# mega.net
KiCad netlist of a schematic drawn in EAGLE
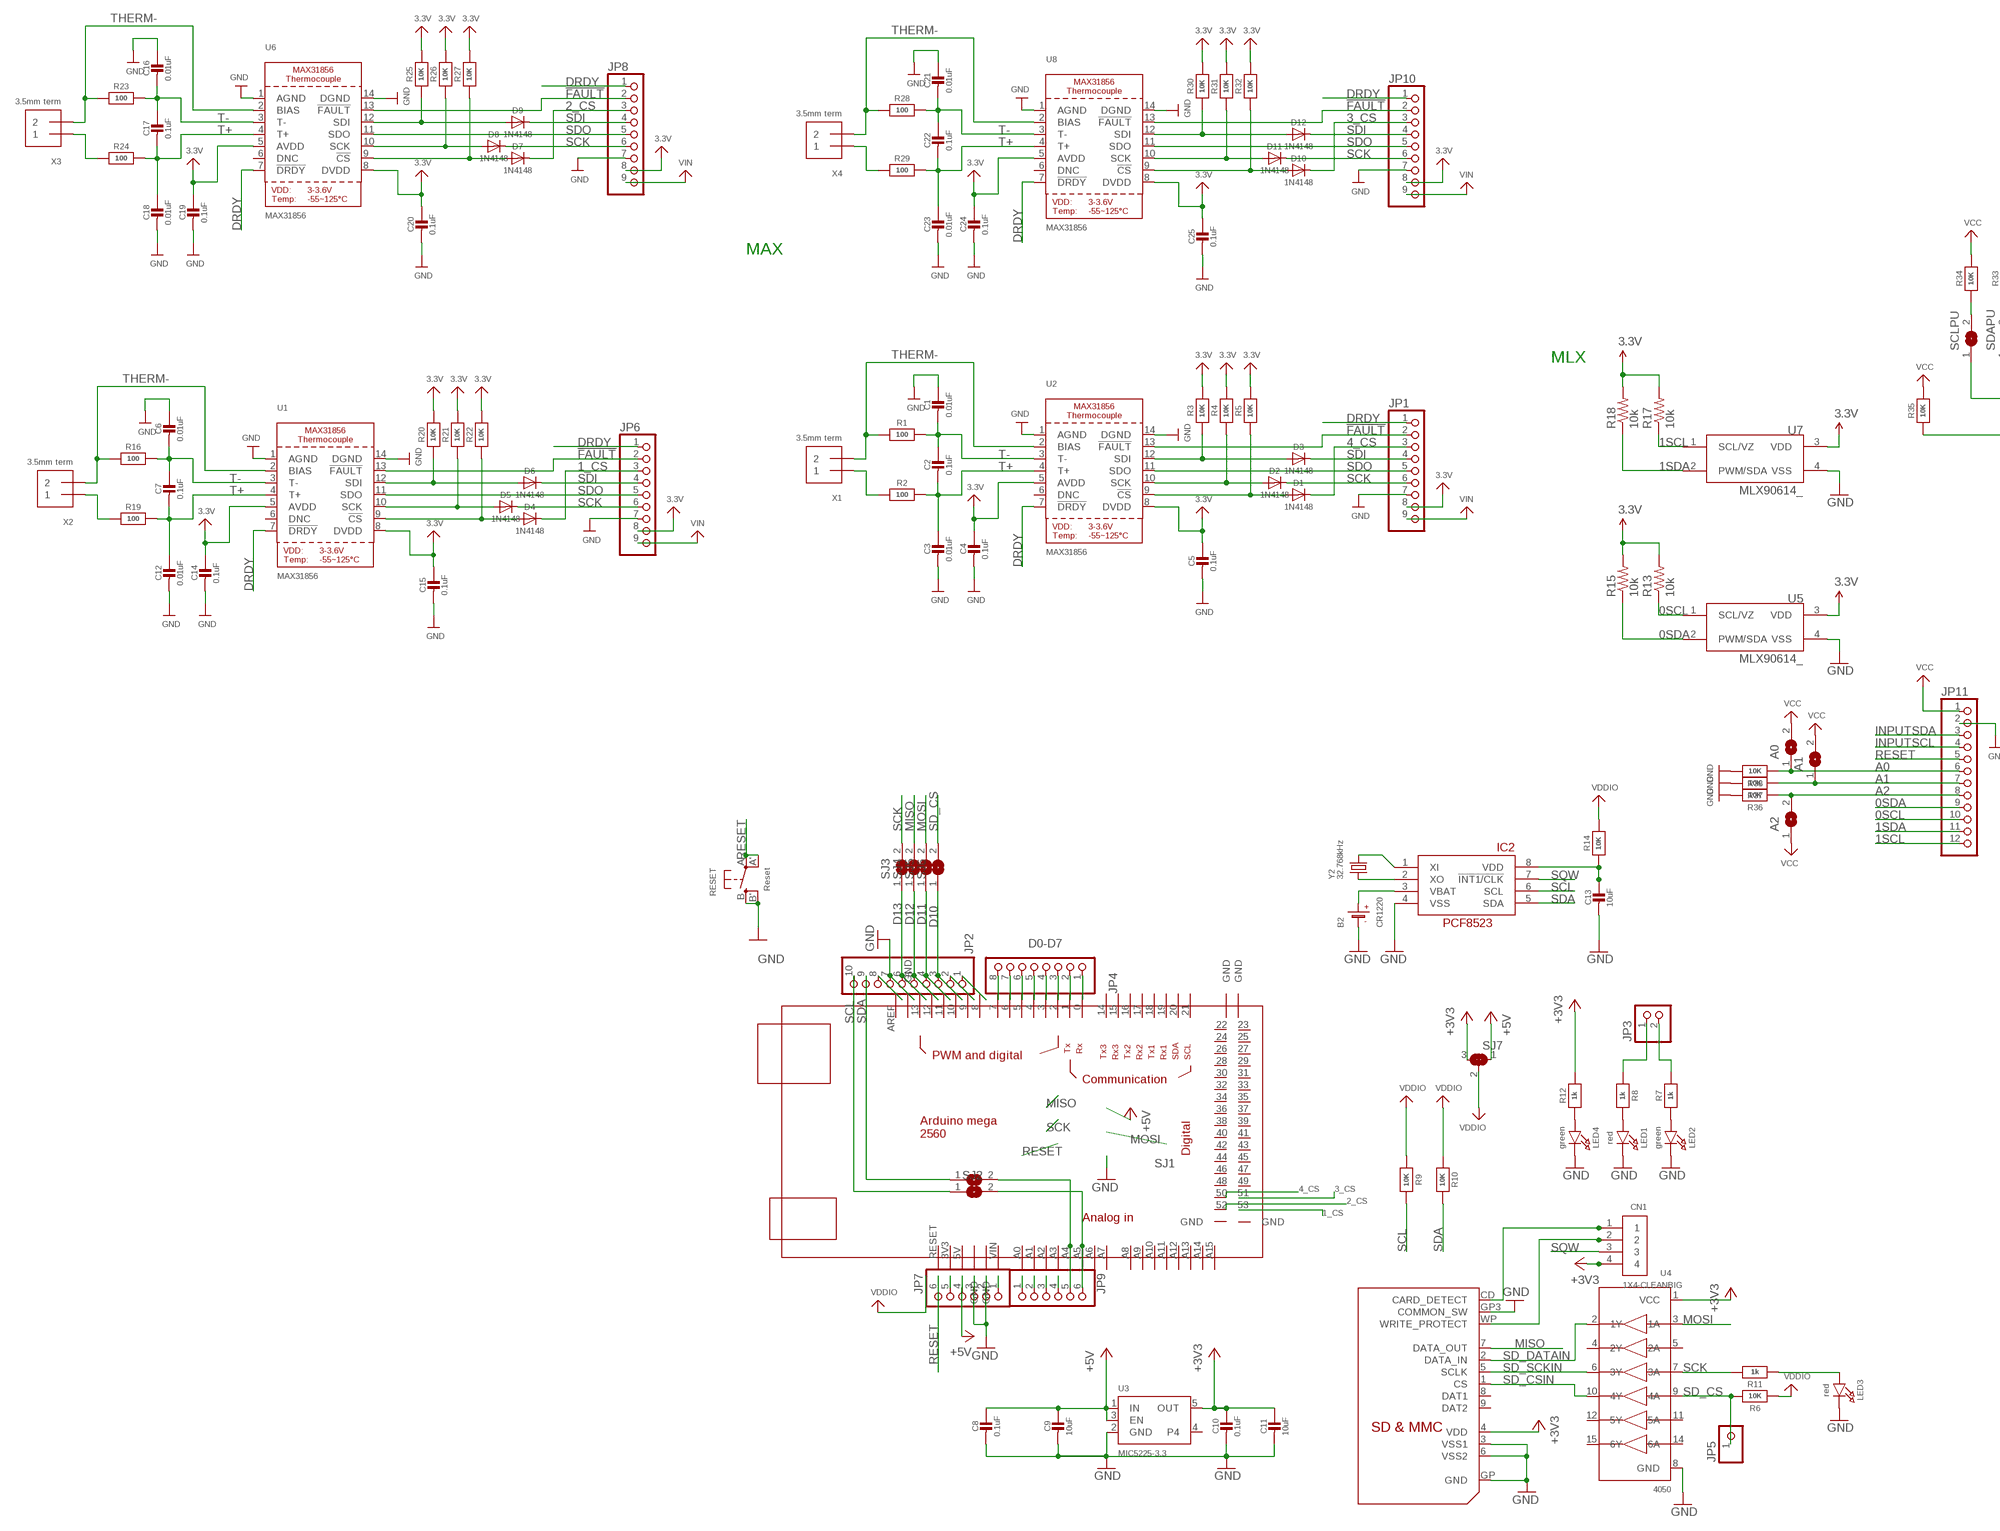
[diagram p0: schematic, sheet 1, part 1 of 2]
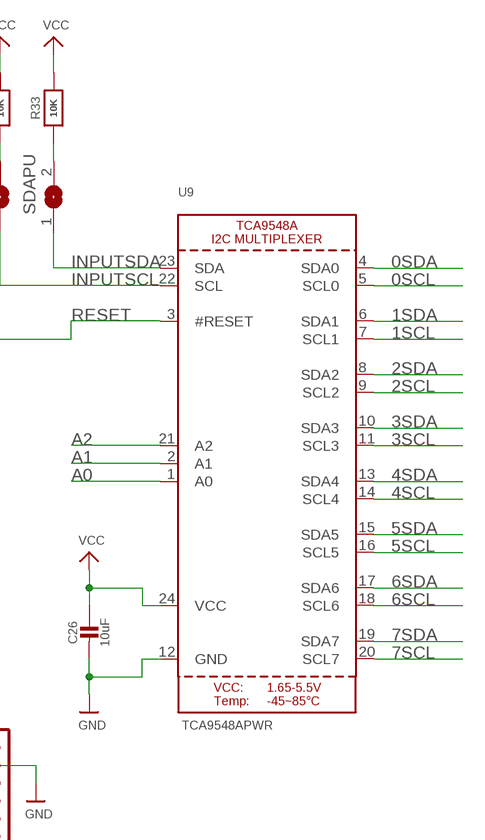
[diagram p1: schematic, sheet 1, part 2 of 2]

(export (version "E")
  (design (tool "Eeschema 10.0.6"))
  (components
    (comp (ref "A0")
      (value "SOLDERJUMPER")
      (footprint "eagle-import:SOLDERJUMPER_ARROW_NOPASTE")
      (libsource (lib "eagle-import") (part "SOLDERJUMPER"))
    )
    (comp (ref "A1")
      (value "SOLDERJUMPER")
      (footprint "eagle-import:SOLDERJUMPER_ARROW_NOPASTE")
      (libsource (lib "eagle-import") (part "SOLDERJUMPER"))
    )
    (comp (ref "A2")
      (value "SOLDERJUMPER")
      (footprint "eagle-import:SOLDERJUMPER_ARROW_NOPASTE")
      (libsource (lib "eagle-import") (part "SOLDERJUMPER"))
    )
    (comp (ref "B2")
      (value "CR1220")
      (footprint "eagle-import:CR1220")
      (libsource (lib "eagle-import") (part "BATTERYCR1220_SMT"))
    )
    (comp (ref "C1")
      (value "0.01uF")
      (footprint "eagle-import:0805_10MGAP")
      (libsource (lib "eagle-import") (part "CAP_CERAMIC0805_10MGAP"))
    )
    (comp (ref "C2")
      (value "0.1uF")
      (footprint "eagle-import:0805-NO")
      (libsource (lib "eagle-import") (part "CAP_CERAMIC0805-NOOUTLINE"))
    )
    (comp (ref "C3")
      (value "0.01uF")
      (footprint "eagle-import:0805-NO")
      (libsource (lib "eagle-import") (part "CAP_CERAMIC0805-NOOUTLINE"))
    )
    (comp (ref "C4")
      (value "0.1uF")
      (footprint "eagle-import:0805-NO")
      (libsource (lib "eagle-import") (part "CAP_CERAMIC0805-NOOUTLINE"))
    )
    (comp (ref "C5")
      (value "0.1uF")
      (footprint "eagle-import:0805-NO")
      (libsource (lib "eagle-import") (part "CAP_CERAMIC0805-NOOUTLINE"))
    )
    (comp (ref "C6")
      (value "0.01uF")
      (footprint "eagle-import:0805_10MGAP")
      (libsource (lib "eagle-import") (part "CAP_CERAMIC0805_10MGAP"))
    )
    (comp (ref "C7")
      (value "0.1uF")
      (footprint "eagle-import:0805-NO")
      (libsource (lib "eagle-import") (part "CAP_CERAMIC0805-NOOUTLINE"))
    )
    (comp (ref "C8")
      (value "0.1uF")
      (footprint "eagle-import:0805-NO")
      (libsource (lib "eagle-import") (part "CAP_CERAMIC0805-NOOUTLINE"))
    )
    (comp (ref "C9")
      (value "10uF")
      (footprint "eagle-import:0805-NO")
      (libsource (lib "eagle-import") (part "CAP_CERAMIC0805-NOOUTLINE"))
    )
    (comp (ref "C10")
      (value "0.1uF")
      (footprint "eagle-import:0805-NO")
      (libsource (lib "eagle-import") (part "CAP_CERAMIC0805-NOOUTLINE"))
    )
    (comp (ref "C11")
      (value "10uF")
      (footprint "eagle-import:0805-NO")
      (libsource (lib "eagle-import") (part "CAP_CERAMIC0805-NOOUTLINE"))
    )
    (comp (ref "C12")
      (value "0.01uF")
      (footprint "eagle-import:0805-NO")
      (libsource (lib "eagle-import") (part "CAP_CERAMIC0805-NOOUTLINE"))
    )
    (comp (ref "C13")
      (value "10uF")
      (footprint "eagle-import:0805-NO")
      (libsource (lib "eagle-import") (part "CAP_CERAMIC0805-NOOUTLINE"))
    )
    (comp (ref "C14")
      (value "0.1uF")
      (footprint "eagle-import:0805-NO")
      (libsource (lib "eagle-import") (part "CAP_CERAMIC0805-NOOUTLINE"))
    )
    (comp (ref "C15")
      (value "0.1uF")
      (footprint "eagle-import:0805-NO")
      (libsource (lib "eagle-import") (part "CAP_CERAMIC0805-NOOUTLINE"))
    )
    (comp (ref "C16")
      (value "0.01uF")
      (footprint "eagle-import:0805_10MGAP")
      (libsource (lib "eagle-import") (part "CAP_CERAMIC0805_10MGAP"))
    )
    (comp (ref "C17")
      (value "0.1uF")
      (footprint "eagle-import:0805-NO")
      (libsource (lib "eagle-import") (part "CAP_CERAMIC0805-NOOUTLINE"))
    )
    (comp (ref "C18")
      (value "0.01uF")
      (footprint "eagle-import:0805-NO")
      (libsource (lib "eagle-import") (part "CAP_CERAMIC0805-NOOUTLINE"))
    )
    (comp (ref "C19")
      (value "0.1uF")
      (footprint "eagle-import:0805-NO")
      (libsource (lib "eagle-import") (part "CAP_CERAMIC0805-NOOUTLINE"))
    )
    (comp (ref "C20")
      (value "0.1uF")
      (footprint "eagle-import:0805-NO")
      (libsource (lib "eagle-import") (part "CAP_CERAMIC0805-NOOUTLINE"))
    )
    (comp (ref "C21")
      (value "0.01uF")
      (footprint "eagle-import:0805_10MGAP")
      (libsource (lib "eagle-import") (part "CAP_CERAMIC0805_10MGAP"))
    )
    (comp (ref "C22")
      (value "0.1uF")
      (footprint "eagle-import:0805-NO")
      (libsource (lib "eagle-import") (part "CAP_CERAMIC0805-NOOUTLINE"))
    )
    (comp (ref "C23")
      (value "0.01uF")
      (footprint "eagle-import:0805-NO")
      (libsource (lib "eagle-import") (part "CAP_CERAMIC0805-NOOUTLINE"))
    )
    (comp (ref "C24")
      (value "0.1uF")
      (footprint "eagle-import:0805-NO")
      (libsource (lib "eagle-import") (part "CAP_CERAMIC0805-NOOUTLINE"))
    )
    (comp (ref "C25")
      (value "0.1uF")
      (footprint "eagle-import:0805-NO")
      (libsource (lib "eagle-import") (part "CAP_CERAMIC0805-NOOUTLINE"))
    )
    (comp (ref "C26")
      (value "10uF")
      (footprint "eagle-import:0805-NO")
      (libsource (lib "eagle-import") (part "CAP_CERAMIC0805-NOOUTLINE"))
    )
    (comp (ref "CN1")
      (value "1X4-CLEANBIG")
      (footprint "eagle-import:1X04-CLEANBIG")
      (libsource (lib "eagle-import") (part "1X4-CLEANBIG"))
    )
    (comp (ref "D1")
      (value "1N4148")
      (footprint "eagle-import:SOD-323")
      (libsource (lib "eagle-import") (part "DIODESOD-323"))
    )
    (comp (ref "D2")
      (value "1N4148")
      (footprint "eagle-import:SOD-323")
      (libsource (lib "eagle-import") (part "DIODESOD-323"))
    )
    (comp (ref "D3")
      (value "1N4148")
      (footprint "eagle-import:SOD-323")
      (libsource (lib "eagle-import") (part "DIODESOD-323"))
    )
    (comp (ref "D4")
      (value "1N4148")
      (footprint "eagle-import:SOD-323")
      (libsource (lib "eagle-import") (part "DIODESOD-323"))
    )
    (comp (ref "D5")
      (value "1N4148")
      (footprint "eagle-import:SOD-323")
      (libsource (lib "eagle-import") (part "DIODESOD-323"))
    )
    (comp (ref "D6")
      (value "1N4148")
      (footprint "eagle-import:SOD-323")
      (libsource (lib "eagle-import") (part "DIODESOD-323"))
    )
    (comp (ref "D7")
      (value "1N4148")
      (footprint "eagle-import:SOD-323")
      (libsource (lib "eagle-import") (part "DIODESOD-323"))
    )
    (comp (ref "D8")
      (value "1N4148")
      (footprint "eagle-import:SOD-323")
      (libsource (lib "eagle-import") (part "DIODESOD-323"))
    )
    (comp (ref "D9")
      (value "1N4148")
      (footprint "eagle-import:SOD-323")
      (libsource (lib "eagle-import") (part "DIODESOD-323"))
    )
    (comp (ref "D10")
      (value "1N4148")
      (footprint "eagle-import:SOD-323")
      (libsource (lib "eagle-import") (part "DIODESOD-323"))
    )
    (comp (ref "D11")
      (value "1N4148")
      (footprint "eagle-import:SOD-323")
      (libsource (lib "eagle-import") (part "DIODESOD-323"))
    )
    (comp (ref "D12")
      (value "1N4148")
      (footprint "eagle-import:SOD-323")
      (libsource (lib "eagle-import") (part "DIODESOD-323"))
    )
    (comp (ref "IC2")
      (value "PCF8523T")
      (footprint "eagle-import:SOIC8_150MIL")
      (libsource (lib "eagle-import") (part "RTC_PCF8523T"))
    )
    (comp (ref "JP1")
      (value "HEADER-1X970MIL")
      (footprint "eagle-import:1X09_ROUND_70")
      (libsource (lib "eagle-import") (part "HEADER-1X970MIL"))
    )
    (comp (ref "JP2")
      (value "HEADER-1X1070MIL")
      (footprint "eagle-import:1X10_ROUND70")
      (libsource (lib "eagle-import") (part "HEADER-1X1070MIL"))
    )
    (comp (ref "JP3")
      (value "HEADER-1X2ROUND")
      (footprint "eagle-import:1X02_ROUND")
      (libsource (lib "eagle-import") (part "HEADER-1X2ROUND"))
    )
    (comp (ref "JP4")
      (value "D0-D7")
      (footprint "eagle-import:1X08-BIG")
      (libsource (lib "eagle-import") (part "PINHD-1X8BIG"))
    )
    (comp (ref "JP5")
      (value "HEADER-1X1ROUND")
      (footprint "eagle-import:1X01_ROUND")
      (libsource (lib "eagle-import") (part "HEADER-1X1ROUND"))
    )
    (comp (ref "JP6")
      (value "HEADER-1X970MIL")
      (footprint "eagle-import:1X09_ROUND_70")
      (libsource (lib "eagle-import") (part "HEADER-1X970MIL"))
    )
    (comp (ref "JP7")
      (value "PINHD-1X6B")
      (footprint "eagle-import:1X06-BIG")
      (libsource (lib "eagle-import") (part "PINHD-1X6B"))
    )
    (comp (ref "JP8")
      (value "HEADER-1X970MIL")
      (footprint "eagle-import:1X09_ROUND_70")
      (libsource (lib "eagle-import") (part "HEADER-1X970MIL"))
    )
    (comp (ref "JP9")
      (value "PINHD-1X6B")
      (footprint "eagle-import:1X06-BIG")
      (libsource (lib "eagle-import") (part "PINHD-1X6B"))
    )
    (comp (ref "JP10")
      (value "HEADER-1X970MIL")
      (footprint "eagle-import:1X09_ROUND_70")
      (libsource (lib "eagle-import") (part "HEADER-1X970MIL"))
    )
    (comp (ref "JP11")
      (value "HEADER-1X12")
      (footprint "eagle-import:1X12_ROUND")
      (libsource (lib "eagle-import") (part "HEADER-1X12"))
    )
    (comp (ref "LED1")
      (value "red")
      (footprint "eagle-import:CHIPLED_0805_NOOUTLINE")
      (libsource (lib "eagle-import") (part "LED0805_NOOUTLINE"))
    )
    (comp (ref "LED2")
      (value "green")
      (footprint "eagle-import:CHIPLED_0805_NOOUTLINE")
      (libsource (lib "eagle-import") (part "LED0805_NOOUTLINE"))
    )
    (comp (ref "LED3")
      (value "red")
      (footprint "eagle-import:CHIPLED_0805_NOOUTLINE")
      (libsource (lib "eagle-import") (part "LED0805_NOOUTLINE"))
    )
    (comp (ref "LED4")
      (value "green")
      (footprint "eagle-import:CHIPLED_0805_NOOUTLINE")
      (libsource (lib "eagle-import") (part "LED0805_NOOUTLINE"))
    )
    (comp (ref "R1")
      (value "100")
      (footprint "eagle-import:0805-NO")
      (libsource (lib "eagle-import") (part "RESISTOR0805_NOOUTLINE"))
    )
    (comp (ref "R2")
      (value "100")
      (footprint "eagle-import:0805-NO")
      (libsource (lib "eagle-import") (part "RESISTOR0805_NOOUTLINE"))
    )
    (comp (ref "R3")
      (value "10K")
      (footprint "eagle-import:0805-NO")
      (libsource (lib "eagle-import") (part "RESISTOR0805_NOOUTLINE"))
    )
    (comp (ref "R4")
      (value "10K")
      (footprint "eagle-import:0805-NO")
      (libsource (lib "eagle-import") (part "RESISTOR0805_NOOUTLINE"))
    )
    (comp (ref "R5")
      (value "10K")
      (footprint "eagle-import:0805-NO")
      (libsource (lib "eagle-import") (part "RESISTOR0805_NOOUTLINE"))
    )
    (comp (ref "R6")
      (value "10K")
      (footprint "eagle-import:0805-NO")
      (libsource (lib "eagle-import") (part "RESISTOR0805_NOOUTLINE"))
    )
    (comp (ref "R7")
      (value "1k")
      (footprint "eagle-import:0805-NO")
      (libsource (lib "eagle-import") (part "RESISTOR0805_NOOUTLINE"))
    )
    (comp (ref "R8")
      (value "1k")
      (footprint "eagle-import:0805-NO")
      (libsource (lib "eagle-import") (part "RESISTOR0805_NOOUTLINE"))
    )
    (comp (ref "R9")
      (value "10K")
      (footprint "eagle-import:0805-NO")
      (libsource (lib "eagle-import") (part "RESISTOR0805_NOOUTLINE"))
    )
    (comp (ref "R10")
      (value "10K")
      (footprint "eagle-import:0805-NO")
      (libsource (lib "eagle-import") (part "RESISTOR0805_NOOUTLINE"))
    )
    (comp (ref "R11")
      (value "1k")
      (footprint "eagle-import:0805-NO")
      (libsource (lib "eagle-import") (part "RESISTOR0805_NOOUTLINE"))
    )
    (comp (ref "R12")
      (value "1k")
      (footprint "eagle-import:0805-NO")
      (libsource (lib "eagle-import") (part "RESISTOR0805_NOOUTLINE"))
    )
    (comp (ref "R13")
      (value "10k")
      (footprint "eagle-import:0402-RES")
      (libsource (lib "eagle-import") (part "RESISTOR0402-RES"))
    )
    (comp (ref "R14")
      (value "10K")
      (footprint "eagle-import:0805-NO")
      (libsource (lib "eagle-import") (part "RESISTOR0805_NOOUTLINE"))
    )
    (comp (ref "R15")
      (value "10k")
      (footprint "eagle-import:0402-RES")
      (libsource (lib "eagle-import") (part "RESISTOR0402-RES"))
    )
    (comp (ref "R16")
      (value "100")
      (footprint "eagle-import:0805-NO")
      (libsource (lib "eagle-import") (part "RESISTOR0805_NOOUTLINE"))
    )
    (comp (ref "R17")
      (value "10k")
      (footprint "eagle-import:0402-RES")
      (libsource (lib "eagle-import") (part "RESISTOR0402-RES"))
    )
    (comp (ref "R18")
      (value "10k")
      (footprint "eagle-import:0402-RES")
      (libsource (lib "eagle-import") (part "RESISTOR0402-RES"))
    )
    (comp (ref "R19")
      (value "100")
      (footprint "eagle-import:0805-NO")
      (libsource (lib "eagle-import") (part "RESISTOR0805_NOOUTLINE"))
    )
    (comp (ref "R20")
      (value "10K")
      (footprint "eagle-import:0805-NO")
      (libsource (lib "eagle-import") (part "RESISTOR0805_NOOUTLINE"))
    )
    (comp (ref "R21")
      (value "10K")
      (footprint "eagle-import:0805-NO")
      (libsource (lib "eagle-import") (part "RESISTOR0805_NOOUTLINE"))
    )
    (comp (ref "R22")
      (value "10K")
      (footprint "eagle-import:0805-NO")
      (libsource (lib "eagle-import") (part "RESISTOR0805_NOOUTLINE"))
    )
    (comp (ref "R23")
      (value "100")
      (footprint "eagle-import:0805-NO")
      (libsource (lib "eagle-import") (part "RESISTOR0805_NOOUTLINE"))
    )
    (comp (ref "R24")
      (value "100")
      (footprint "eagle-import:0805-NO")
      (libsource (lib "eagle-import") (part "RESISTOR0805_NOOUTLINE"))
    )
    (comp (ref "R25")
      (value "10K")
      (footprint "eagle-import:0805-NO")
      (libsource (lib "eagle-import") (part "RESISTOR0805_NOOUTLINE"))
    )
    (comp (ref "R26")
      (value "10K")
      (footprint "eagle-import:0805-NO")
      (libsource (lib "eagle-import") (part "RESISTOR0805_NOOUTLINE"))
    )
    (comp (ref "R27")
      (value "10K")
      (footprint "eagle-import:0805-NO")
      (libsource (lib "eagle-import") (part "RESISTOR0805_NOOUTLINE"))
    )
    (comp (ref "R28")
      (value "100")
      (footprint "eagle-import:0805-NO")
      (libsource (lib "eagle-import") (part "RESISTOR0805_NOOUTLINE"))
    )
    (comp (ref "R29")
      (value "100")
      (footprint "eagle-import:0805-NO")
      (libsource (lib "eagle-import") (part "RESISTOR0805_NOOUTLINE"))
    )
    (comp (ref "R30")
      (value "10K")
      (footprint "eagle-import:0805-NO")
      (libsource (lib "eagle-import") (part "RESISTOR0805_NOOUTLINE"))
    )
    (comp (ref "R31")
      (value "10K")
      (footprint "eagle-import:0805-NO")
      (libsource (lib "eagle-import") (part "RESISTOR0805_NOOUTLINE"))
    )
    (comp (ref "R32")
      (value "10K")
      (footprint "eagle-import:0805-NO")
      (libsource (lib "eagle-import") (part "RESISTOR0805_NOOUTLINE"))
    )
    (comp (ref "R33")
      (value "10K")
      (footprint "eagle-import:0805-NO")
      (libsource (lib "eagle-import") (part "RESISTOR0805_NOOUTLINE"))
    )
    (comp (ref "R34")
      (value "10K")
      (footprint "eagle-import:0805-NO")
      (libsource (lib "eagle-import") (part "RESISTOR0805_NOOUTLINE"))
    )
    (comp (ref "R35")
      (value "10K")
      (footprint "eagle-import:_0805MP")
      (libsource (lib "eagle-import") (part "RESISTOR_0805MP"))
    )
    (comp (ref "R36")
      (value "10K")
      (footprint "eagle-import:0805-NO")
      (libsource (lib "eagle-import") (part "RESISTOR0805_NOOUTLINE"))
    )
    (comp (ref "R37")
      (value "10K")
      (footprint "eagle-import:0805-NO")
      (libsource (lib "eagle-import") (part "RESISTOR0805_NOOUTLINE"))
    )
    (comp (ref "R38")
      (value "10K")
      (footprint "eagle-import:0805-NO")
      (libsource (lib "eagle-import") (part "RESISTOR0805_NOOUTLINE"))
    )
    (comp (ref "RESET")
      (value "Reset")
      (footprint "eagle-import:EVQ-Q2_SMALLER")
      (libsource (lib "eagle-import") (part "SWITCH_TACT_SMT_EVQQ2_SMALL"))
    )
    (comp (ref "SCLPU")
      (value "SOLDERJUMPERCLOSED")
      (footprint "eagle-import:SOLDERJUMPER_CLOSEDWIRE")
      (libsource (lib "eagle-import") (part "SOLDERJUMPERCLOSED"))
    )
    (comp (ref "SDAPU")
      (value "SOLDERJUMPERCLOSED")
      (footprint "eagle-import:SOLDERJUMPER_CLOSEDWIRE")
      (libsource (lib "eagle-import") (part "SOLDERJUMPERCLOSED"))
    )
    (comp (ref "SJ1")
      (value "SOLDERJUMPER")
      (footprint "eagle-import:SOLDERJUMPER_ARROW_NOPASTE")
      (libsource (lib "eagle-import") (part "SOLDERJUMPER"))
    )
    (comp (ref "SJ2")
      (value "SOLDERJUMPER")
      (footprint "eagle-import:SOLDERJUMPER_ARROW_NOPASTE")
      (libsource (lib "eagle-import") (part "SOLDERJUMPER"))
    )
    (comp (ref "SJ3")
      (value "SOLDERJUMPER")
      (footprint "eagle-import:SOLDERJUMPER_ARROW_NOPASTE")
      (libsource (lib "eagle-import") (part "SOLDERJUMPER"))
    )
    (comp (ref "SJ4")
      (value "SOLDERJUMPER")
      (footprint "eagle-import:SOLDERJUMPER_ARROW_NOPASTE")
      (libsource (lib "eagle-import") (part "SOLDERJUMPER"))
    )
    (comp (ref "SJ5")
      (value "SOLDERJUMPER")
      (footprint "eagle-import:SOLDERJUMPER_ARROW_NOPASTE")
      (libsource (lib "eagle-import") (part "SOLDERJUMPER"))
    )
    (comp (ref "SJ6")
      (value "SOLDERJUMPERCLOSED")
      (footprint "eagle-import:SOLDERJUMPER_CLOSEDWIRE")
      (libsource (lib "eagle-import") (part "SOLDERJUMPERCLOSED"))
    )
    (comp (ref "SJ7")
      (value "SOLDERJUMPER_2WAY")
      (footprint "eagle-import:SOLDERJUMPER_2WAY_OPEN_NOPASTE")
      (libsource (lib "eagle-import") (part "SOLDERJUMPER_2WAY"))
    )
    (comp (ref "U$1")
      (value "MEGA_DEVICE")
      (footprint "eagle-import:MEGAOUTLINE")
      (libsource (lib "eagle-import") (part "MEGA_DEVICE"))
    )
    (comp (ref "U$14")
      (value "SDMMC06132")
      (footprint "eagle-import:06132")
      (libsource (lib "eagle-import") (part "SDMMC06132"))
    )
    (comp (ref "U1")
      (value "MAX31856")
      (footprint "eagle-import:TSSOP14")
      (libsource (lib "eagle-import") (part "MAX31856"))
    )
    (comp (ref "U2")
      (value "MAX31856")
      (footprint "eagle-import:TSSOP14")
      (libsource (lib "eagle-import") (part "MAX31856"))
    )
    (comp (ref "U3")
      (value "MIC5225-3.3")
      (footprint "eagle-import:SOT23-5")
      (libsource (lib "eagle-import") (part "VREG_SOT23-5"))
    )
    (comp (ref "U4")
      (value "4050")
      (footprint "eagle-import:SOIC16")
      (libsource (lib "eagle-import") (part "74HC4050D"))
    )
    (comp (ref "U5")
      (value "MLX90614_")
      (footprint "eagle-import:TO-39")
      (libsource (lib "eagle-import") (part "MLX90614_"))
    )
    (comp (ref "U6")
      (value "MAX31856")
      (footprint "eagle-import:TSSOP14")
      (libsource (lib "eagle-import") (part "MAX31856"))
    )
    (comp (ref "U7")
      (value "MLX90614_")
      (footprint "eagle-import:TO-39")
      (libsource (lib "eagle-import") (part "MLX90614_"))
    )
    (comp (ref "U8")
      (value "MAX31856")
      (footprint "eagle-import:TSSOP14")
      (libsource (lib "eagle-import") (part "MAX31856"))
    )
    (comp (ref "U9")
      (value "TCA9548APWR")
      (footprint "eagle-import:TSSOP24")
      (libsource (lib "eagle-import") (part "TCA9548A"))
    )
    (comp (ref "X1")
      (value "3.5mm term")
      (footprint "eagle-import:TERMBLOCK_1X2-3.5MM")
      (libsource (lib "eagle-import") (part "TERMBLOCK_1X2"))
    )
    (comp (ref "X2")
      (value "3.5mm term")
      (footprint "eagle-import:TERMBLOCK_1X2-3.5MM")
      (libsource (lib "eagle-import") (part "TERMBLOCK_1X2"))
    )
    (comp (ref "X3")
      (value "3.5mm term")
      (footprint "eagle-import:TERMBLOCK_1X2-3.5MM")
      (libsource (lib "eagle-import") (part "TERMBLOCK_1X2"))
    )
    (comp (ref "X4")
      (value "3.5mm term")
      (footprint "eagle-import:TERMBLOCK_1X2-3.5MM")
      (libsource (lib "eagle-import") (part "TERMBLOCK_1X2"))
    )
    (comp (ref "Y2")
      (value "32.768kHz")
      (footprint "eagle-import:CRYSTAL_8X3.8")
      (libsource (lib "eagle-import") (part "CRYSTAL8.0X3.8"))
    )
  )
  (nets
    (net (code "1") (name "+3V3") (class "Default")
      (node (ref "C10") (pin "1") (pinfunction "1_1") (pintype "passive"))
      (node (ref "C11") (pin "1") (pinfunction "1_1") (pintype "passive"))
      (node (ref "CN1") (pin "4") (pinfunction "4_4") (pintype "bidirectional"))
      (node (ref "R12") (pin "2") (pinfunction "2_2") (pintype "passive"))
      (node (ref "SJ7") (pin "3") (pinfunction "3_3") (pintype "passive"))
      (node (ref "U$14") (pin "4") (pinfunction "VDD_4") (pintype "power_in"))
      (node (ref "U3") (pin "5") (pinfunction "OUT_5") (pintype "power_in"))
      (node (ref "U4") (pin "1") (pinfunction "VCC_1") (pintype "bidirectional"))
    )
    (net (code "2") (name "+5V") (class "Default")
      (node (ref "C8") (pin "1") (pinfunction "1_1") (pintype "passive"))
      (node (ref "C9") (pin "1") (pinfunction "1_1") (pintype "passive"))
      (node (ref "JP7") (pin "4") (pinfunction "4_4") (pintype "passive"))
      (node (ref "SJ7") (pin "1") (pinfunction "1_1") (pintype "passive"))
      (node (ref "U3") (pin "1") (pinfunction "IN_1") (pintype "power_in"))
      (node (ref "U3") (pin "3") (pinfunction "EN_3") (pintype "input"))
    )
    (net (code "3") (name "/0SCL") (class "Default")
      (node (ref "JP11") (pin "10") (pinfunction "10_10") (pintype "passive"))
      (node (ref "R13") (pin "1") (pinfunction "1_1") (pintype "passive"))
      (node (ref "U5") (pin "1") (pinfunction "SCL/VZ_1") (pintype "bidirectional"))
      (node (ref "U9") (pin "5") (pinfunction "SCL0_5") (pintype "bidirectional"))
    )
    (net (code "4") (name "/0SDA") (class "Default")
      (node (ref "JP11") (pin "9") (pinfunction "9_9") (pintype "passive"))
      (node (ref "R15") (pin "1") (pinfunction "1_1") (pintype "passive"))
      (node (ref "U5") (pin "2") (pinfunction "PWM/SDA_2") (pintype "bidirectional"))
      (node (ref "U9") (pin "4") (pinfunction "SDA0_4") (pintype "bidirectional"))
    )
    (net (code "5") (name "/1SCL") (class "Default")
      (node (ref "JP11") (pin "12") (pinfunction "12_12") (pintype "passive"))
      (node (ref "R17") (pin "1") (pinfunction "1_1") (pintype "passive"))
      (node (ref "U7") (pin "1") (pinfunction "SCL/VZ_1") (pintype "bidirectional"))
      (node (ref "U9") (pin "7") (pinfunction "SCL1_7") (pintype "bidirectional"))
    )
    (net (code "6") (name "/1SDA") (class "Default")
      (node (ref "JP11") (pin "11") (pinfunction "11_11") (pintype "passive"))
      (node (ref "R18") (pin "1") (pinfunction "1_1") (pintype "passive"))
      (node (ref "U7") (pin "2") (pinfunction "PWM/SDA_2") (pintype "bidirectional"))
      (node (ref "U9") (pin "6") (pinfunction "SDA1_6") (pintype "bidirectional"))
    )
    (net (code "7") (name "/1_CS") (class "Default")
      (node (ref "D4") (pin "C") (pinfunction "C_C") (pintype "passive"))
      (node (ref "JP6") (pin "3") (pinfunction "3_3") (pintype "passive"))
      (node (ref "U$1") (pin "53") (pinfunction "53_53") (pintype "bidirectional"))
    )
    (net (code "8") (name "/2SCL") (class "Default")
      (node (ref "U9") (pin "9") (pinfunction "SCL2_9") (pintype "bidirectional"))
    )
    (net (code "9") (name "/2SDA") (class "Default")
      (node (ref "U9") (pin "8") (pinfunction "SDA2_8") (pintype "bidirectional"))
    )
    (net (code "10") (name "/2_CS") (class "Default")
      (node (ref "D7") (pin "C") (pinfunction "C_C") (pintype "passive"))
      (node (ref "JP8") (pin "3") (pinfunction "3_3") (pintype "passive"))
      (node (ref "U$1") (pin "52") (pinfunction "52_52") (pintype "bidirectional"))
    )
    (net (code "11") (name "/3SCL") (class "Default")
      (node (ref "U9") (pin "11") (pinfunction "SCL3_11") (pintype "bidirectional"))
    )
    (net (code "12") (name "/3SDA") (class "Default")
      (node (ref "U9") (pin "10") (pinfunction "SDA3_10") (pintype "bidirectional"))
    )
    (net (code "13") (name "/3_CS") (class "Default")
      (node (ref "D10") (pin "C") (pinfunction "C_C") (pintype "passive"))
      (node (ref "JP10") (pin "3") (pinfunction "3_3") (pintype "passive"))
      (node (ref "U$1") (pin "51") (pinfunction "51_51") (pintype "bidirectional"))
    )
    (net (code "14") (name "/4SCL") (class "Default")
      (node (ref "U9") (pin "14") (pinfunction "SCL4_14") (pintype "bidirectional"))
    )
    (net (code "15") (name "/4SDA") (class "Default")
      (node (ref "U9") (pin "13") (pinfunction "SDA4_13") (pintype "bidirectional"))
    )
    (net (code "16") (name "/4_CS") (class "Default")
      (node (ref "D1") (pin "C") (pinfunction "C_C") (pintype "passive"))
      (node (ref "JP1") (pin "3") (pinfunction "3_3") (pintype "passive"))
      (node (ref "U$1") (pin "50") (pinfunction "50_50") (pintype "bidirectional"))
    )
    (net (code "17") (name "/5SCL") (class "Default")
      (node (ref "U9") (pin "16") (pinfunction "SCL5_16") (pintype "bidirectional"))
    )
    (net (code "18") (name "/5SDA") (class "Default")
      (node (ref "U9") (pin "15") (pinfunction "SDA5_15") (pintype "bidirectional"))
    )
    (net (code "19") (name "/6SCL") (class "Default")
      (node (ref "U9") (pin "18") (pinfunction "SCL6_18") (pintype "bidirectional"))
    )
    (net (code "20") (name "/6SDA") (class "Default")
      (node (ref "U9") (pin "17") (pinfunction "SDA6_17") (pintype "bidirectional"))
    )
    (net (code "21") (name "/7SCL") (class "Default")
      (node (ref "U9") (pin "20") (pinfunction "SCL7_20") (pintype "bidirectional"))
    )
    (net (code "22") (name "/7SDA") (class "Default")
      (node (ref "U9") (pin "19") (pinfunction "SDA7_19") (pintype "bidirectional"))
    )
    (net (code "23") (name "/A0") (class "Default")
      (node (ref "A0") (pin "1") (pinfunction "1_1") (pintype "passive"))
      (node (ref "JP11") (pin "6") (pinfunction "6_6") (pintype "passive"))
      (node (ref "R38") (pin "1") (pinfunction "1_1") (pintype "passive"))
      (node (ref "U9") (pin "1") (pinfunction "A0_1") (pintype "bidirectional"))
    )
    (net (code "24") (name "/A1") (class "Default")
      (node (ref "A1") (pin "1") (pinfunction "1_1") (pintype "passive"))
      (node (ref "JP11") (pin "7") (pinfunction "7_7") (pintype "passive"))
      (node (ref "R37") (pin "1") (pinfunction "1_1") (pintype "passive"))
      (node (ref "U9") (pin "2") (pinfunction "A1_2") (pintype "bidirectional"))
    )
    (net (code "25") (name "/A2") (class "Default")
      (node (ref "A2") (pin "2") (pinfunction "2_2") (pintype "passive"))
      (node (ref "JP11") (pin "8") (pinfunction "8_8") (pintype "passive"))
      (node (ref "R36") (pin "1") (pinfunction "1_1") (pintype "passive"))
      (node (ref "U9") (pin "21") (pinfunction "A2_21") (pintype "bidirectional"))
    )
    (net (code "26") (name "/D10") (class "Default")
      (node (ref "JP2") (pin "3") (pinfunction "3_3") (pintype "passive"))
      (node (ref "SJ6") (pin "1") (pinfunction "1_1") (pintype "passive"))
    )
    (net (code "27") (name "/D11") (class "Default")
      (node (ref "JP2") (pin "4") (pinfunction "4_4") (pintype "passive"))
      (node (ref "SJ5") (pin "1") (pinfunction "1_1") (pintype "passive"))
    )
    (net (code "28") (name "/D12") (class "Default")
      (node (ref "JP2") (pin "5") (pinfunction "5_5") (pintype "passive"))
      (node (ref "SJ4") (pin "1") (pinfunction "1_1") (pintype "passive"))
    )
    (net (code "29") (name "/D13") (class "Default")
      (node (ref "JP2") (pin "6") (pinfunction "6_6") (pintype "passive"))
      (node (ref "SJ3") (pin "1") (pinfunction "1_1") (pintype "passive"))
    )
    (net (code "30") (name "/DRDY") (class "Default")
      (node (ref "JP1") (pin "1") (pinfunction "1_1") (pintype "passive"))
      (node (ref "JP10") (pin "1") (pinfunction "1_1") (pintype "passive"))
      (node (ref "JP6") (pin "1") (pinfunction "1_1") (pintype "passive"))
      (node (ref "JP8") (pin "1") (pinfunction "1_1") (pintype "passive"))
      (node (ref "U1") (pin "7") (pinfunction "~{DRDY}_7") (pintype "output"))
      (node (ref "U2") (pin "7") (pinfunction "~{DRDY}_7") (pintype "output"))
      (node (ref "U6") (pin "7") (pinfunction "~{DRDY}_7") (pintype "output"))
      (node (ref "U8") (pin "7") (pinfunction "~{DRDY}_7") (pintype "output"))
    )
    (net (code "31") (name "/INPUTSCL") (class "Default")
      (node (ref "JP11") (pin "4") (pinfunction "4_4") (pintype "passive"))
      (node (ref "SCLPU") (pin "1") (pinfunction "1_1") (pintype "passive"))
      (node (ref "U9") (pin "22") (pinfunction "SCL_22") (pintype "bidirectional"))
    )
    (net (code "32") (name "/INPUTSDA") (class "Default")
      (node (ref "JP11") (pin "3") (pinfunction "3_3") (pintype "passive"))
      (node (ref "SDAPU") (pin "1") (pinfunction "1_1") (pintype "passive"))
      (node (ref "U9") (pin "23") (pinfunction "SDA_23") (pintype "bidirectional"))
    )
    (net (code "33") (name "/MISO") (class "Default")
      (node (ref "SJ4") (pin "2") (pinfunction "2_2") (pintype "passive"))
      (node (ref "U$14") (pin "7") (pinfunction "DATA_OUT_7") (pintype "output"))
    )
    (net (code "34") (name "/MOSI") (class "Default")
      (node (ref "SJ5") (pin "2") (pinfunction "2_2") (pintype "passive"))
      (node (ref "U4") (pin "3") (pinfunction "1A_3") (pintype "bidirectional"))
    )
    (net (code "35") (name "/RESET") (class "Default")
      (node (ref "JP11") (pin "5") (pinfunction "5_5") (pintype "passive"))
      (node (ref "JP7") (pin "6") (pinfunction "6_6") (pintype "passive"))
      (node (ref "R35") (pin "1") (pinfunction "1_1") (pintype "passive"))
      (node (ref "RESET") (pin "A") (pinfunction "P_A") (pintype "passive"))
      (node (ref "RESET") (pin "A'") (pinfunction "P1_A'") (pintype "passive"))
      (node (ref "U9") (pin "3") (pinfunction "#RESET_3") (pintype "bidirectional"))
    )
    (net (code "36") (name "/SCK") (class "Default")
      (node (ref "D11") (pin "C") (pinfunction "C_C") (pintype "passive"))
      (node (ref "D2") (pin "C") (pinfunction "C_C") (pintype "passive"))
      (node (ref "D5") (pin "C") (pinfunction "C_C") (pintype "passive"))
      (node (ref "D8") (pin "C") (pinfunction "C_C") (pintype "passive"))
      (node (ref "JP1") (pin "6") (pinfunction "6_6") (pintype "passive"))
      (node (ref "JP10") (pin "6") (pinfunction "6_6") (pintype "passive"))
      (node (ref "JP6") (pin "6") (pinfunction "6_6") (pintype "passive"))
      (node (ref "JP8") (pin "6") (pinfunction "6_6") (pintype "passive"))
      (node (ref "R11") (pin "2") (pinfunction "2_2") (pintype "passive"))
      (node (ref "SJ3") (pin "2") (pinfunction "2_2") (pintype "passive"))
      (node (ref "U4") (pin "7") (pinfunction "3A_7") (pintype "bidirectional"))
    )
    (net (code "37") (name "/SCL") (class "Default")
      (node (ref "IC2") (pin "6") (pinfunction "SCL_6") (pintype "bidirectional"))
      (node (ref "JP2") (pin "10") (pinfunction "10_10") (pintype "passive"))
      (node (ref "R9") (pin "2") (pinfunction "2_2") (pintype "passive"))
      (node (ref "SJ2") (pin "1") (pinfunction "1_1") (pintype "passive"))
    )
    (net (code "38") (name "/SDA") (class "Default")
      (node (ref "IC2") (pin "5") (pinfunction "SDA_5") (pintype "bidirectional"))
      (node (ref "JP2") (pin "9") (pinfunction "9_9") (pintype "passive"))
      (node (ref "R10") (pin "2") (pinfunction "2_2") (pintype "passive"))
      (node (ref "SJ1") (pin "1") (pinfunction "1_1") (pintype "passive"))
    )
    (net (code "39") (name "/SDI") (class "Default")
      (node (ref "D12") (pin "C") (pinfunction "C_C") (pintype "passive"))
      (node (ref "D3") (pin "C") (pinfunction "C_C") (pintype "passive"))
      (node (ref "D6") (pin "C") (pinfunction "C_C") (pintype "passive"))
      (node (ref "D9") (pin "C") (pinfunction "C_C") (pintype "passive"))
      (node (ref "JP1") (pin "4") (pinfunction "4_4") (pintype "passive"))
      (node (ref "JP10") (pin "4") (pinfunction "4_4") (pintype "passive"))
      (node (ref "JP6") (pin "4") (pinfunction "4_4") (pintype "passive"))
      (node (ref "JP8") (pin "4") (pinfunction "4_4") (pintype "passive"))
    )
    (net (code "40") (name "/SDO") (class "Default")
      (node (ref "JP1") (pin "5") (pinfunction "5_5") (pintype "passive"))
      (node (ref "JP10") (pin "5") (pinfunction "5_5") (pintype "passive"))
      (node (ref "JP6") (pin "5") (pinfunction "5_5") (pintype "passive"))
      (node (ref "JP8") (pin "5") (pinfunction "5_5") (pintype "passive"))
      (node (ref "U1") (pin "11") (pinfunction "SDO_11") (pintype "output"))
      (node (ref "U2") (pin "11") (pinfunction "SDO_11") (pintype "output"))
      (node (ref "U6") (pin "11") (pinfunction "SDO_11") (pintype "output"))
      (node (ref "U8") (pin "11") (pinfunction "SDO_11") (pintype "output"))
    )
    (net (code "41") (name "/SD_CS") (class "Default")
      (node (ref "JP5") (pin "1") (pinfunction "1_1") (pintype "passive"))
      (node (ref "R6") (pin "2") (pinfunction "2_2") (pintype "passive"))
      (node (ref "SJ6") (pin "2") (pinfunction "2_2") (pintype "passive"))
      (node (ref "U4") (pin "9") (pinfunction "4A_9") (pintype "bidirectional"))
    )
    (net (code "42") (name "/SD_CSIN") (class "Default")
      (node (ref "U$14") (pin "1") (pinfunction "CS_1") (pintype "input"))
      (node (ref "U4") (pin "10") (pinfunction "4Y_10") (pintype "bidirectional"))
    )
    (net (code "43") (name "/SD_DATAIN") (class "Default")
      (node (ref "U$14") (pin "2") (pinfunction "DATA_IN_2") (pintype "input"))
      (node (ref "U4") (pin "2") (pinfunction "1Y_2") (pintype "bidirectional"))
    )
    (net (code "44") (name "/SD_SCKIN") (class "Default")
      (node (ref "U$14") (pin "5") (pinfunction "SCLK_5") (pintype "input"))
      (node (ref "U4") (pin "6") (pinfunction "3Y_6") (pintype "bidirectional"))
    )
    (net (code "45") (name "/SQW") (class "Default")
      (node (ref "CN1") (pin "3") (pinfunction "3_3") (pintype "bidirectional"))
      (node (ref "IC2") (pin "7") (pinfunction "~{INT1/CLK}_7") (pintype "output"))
    )
    (net (code "46") (name "/T+") (class "Default")
      (node (ref "C12") (pin "1") (pinfunction "1_1") (pintype "passive"))
      (node (ref "C17") (pin "2") (pinfunction "2_2") (pintype "passive"))
      (node (ref "C18") (pin "1") (pinfunction "1_1") (pintype "passive"))
      (node (ref "C2") (pin "2") (pinfunction "2_2") (pintype "passive"))
      (node (ref "C22") (pin "2") (pinfunction "2_2") (pintype "passive"))
      (node (ref "C23") (pin "1") (pinfunction "1_1") (pintype "passive"))
      (node (ref "C3") (pin "1") (pinfunction "1_1") (pintype "passive"))
      (node (ref "C7") (pin "2") (pinfunction "2_2") (pintype "passive"))
      (node (ref "R19") (pin "2") (pinfunction "2_2") (pintype "passive"))
      (node (ref "R2") (pin "2") (pinfunction "2_2") (pintype "passive"))
      (node (ref "R24") (pin "2") (pinfunction "2_2") (pintype "passive"))
      (node (ref "R29") (pin "2") (pinfunction "2_2") (pintype "passive"))
      (node (ref "U1") (pin "4") (pinfunction "T+_4") (pintype "input"))
      (node (ref "U2") (pin "4") (pinfunction "T+_4") (pintype "input"))
      (node (ref "U6") (pin "4") (pinfunction "T+_4") (pintype "input"))
      (node (ref "U8") (pin "4") (pinfunction "T+_4") (pintype "input"))
    )
    (net (code "47") (name "/T-") (class "Default")
      (node (ref "C1") (pin "2") (pinfunction "2_2") (pintype "passive"))
      (node (ref "C16") (pin "2") (pinfunction "2_2") (pintype "passive"))
      (node (ref "C17") (pin "1") (pinfunction "1_1") (pintype "passive"))
      (node (ref "C2") (pin "1") (pinfunction "1_1") (pintype "passive"))
      (node (ref "C21") (pin "2") (pinfunction "2_2") (pintype "passive"))
      (node (ref "C22") (pin "1") (pinfunction "1_1") (pintype "passive"))
      (node (ref "C6") (pin "2") (pinfunction "2_2") (pintype "passive"))
      (node (ref "C7") (pin "1") (pinfunction "1_1") (pintype "passive"))
      (node (ref "R1") (pin "2") (pinfunction "2_2") (pintype "passive"))
      (node (ref "R16") (pin "2") (pinfunction "2_2") (pintype "passive"))
      (node (ref "R23") (pin "2") (pinfunction "2_2") (pintype "passive"))
      (node (ref "R28") (pin "2") (pinfunction "2_2") (pintype "passive"))
      (node (ref "U1") (pin "3") (pinfunction "T-_3") (pintype "input"))
      (node (ref "U2") (pin "3") (pinfunction "T-_3") (pintype "input"))
      (node (ref "U6") (pin "3") (pinfunction "T-_3") (pintype "input"))
      (node (ref "U8") (pin "3") (pinfunction "T-_3") (pintype "input"))
    )
    (net (code "48") (name "/THERM-") (class "Default")
      (node (ref "R1") (pin "1") (pinfunction "1_1") (pintype "passive"))
      (node (ref "R16") (pin "1") (pinfunction "1_1") (pintype "passive"))
      (node (ref "R23") (pin "1") (pinfunction "1_1") (pintype "passive"))
      (node (ref "R28") (pin "1") (pinfunction "1_1") (pintype "passive"))
      (node (ref "U1") (pin "2") (pinfunction "BIAS_2") (pintype "power_in"))
      (node (ref "U2") (pin "2") (pinfunction "BIAS_2") (pintype "power_in"))
      (node (ref "U6") (pin "2") (pinfunction "BIAS_2") (pintype "power_in"))
      (node (ref "U8") (pin "2") (pinfunction "BIAS_2") (pintype "power_in"))
      (node (ref "X1") (pin "2") (pinfunction "2_2") (pintype "passive"))
      (node (ref "X2") (pin "2") (pinfunction "2_2") (pintype "passive"))
      (node (ref "X3") (pin "2") (pinfunction "2_2") (pintype "passive"))
      (node (ref "X4") (pin "2") (pinfunction "2_2") (pintype "passive"))
    )
    (net (code "49") (name "/~{FAULT}") (class "Default")
      (node (ref "JP1") (pin "2") (pinfunction "2_2") (pintype "passive"))
      (node (ref "JP10") (pin "2") (pinfunction "2_2") (pintype "passive"))
      (node (ref "JP6") (pin "2") (pinfunction "2_2") (pintype "passive"))
      (node (ref "JP8") (pin "2") (pinfunction "2_2") (pintype "passive"))
      (node (ref "U1") (pin "13") (pinfunction "~{FAULT}_13") (pintype "output"))
      (node (ref "U2") (pin "13") (pinfunction "~{FAULT}_13") (pintype "output"))
      (node (ref "U6") (pin "13") (pinfunction "~{FAULT}_13") (pintype "output"))
      (node (ref "U8") (pin "13") (pinfunction "~{FAULT}_13") (pintype "output"))
    )
    (net (code "50") (name "3.3V") (class "Default")
      (node (ref "C14") (pin "1") (pinfunction "1_1") (pintype "passive"))
      (node (ref "C15") (pin "1") (pinfunction "1_1") (pintype "passive"))
      (node (ref "C19") (pin "1") (pinfunction "1_1") (pintype "passive"))
      (node (ref "C20") (pin "1") (pinfunction "1_1") (pintype "passive"))
      (node (ref "C24") (pin "1") (pinfunction "1_1") (pintype "passive"))
      (node (ref "C25") (pin "1") (pinfunction "1_1") (pintype "passive"))
      (node (ref "C4") (pin "1") (pinfunction "1_1") (pintype "passive"))
      (node (ref "C5") (pin "1") (pinfunction "1_1") (pintype "passive"))
      (node (ref "JP1") (pin "8") (pinfunction "8_8") (pintype "passive"))
      (node (ref "JP10") (pin "8") (pinfunction "8_8") (pintype "passive"))
      (node (ref "JP6") (pin "8") (pinfunction "8_8") (pintype "passive"))
      (node (ref "JP8") (pin "8") (pinfunction "8_8") (pintype "passive"))
      (node (ref "R13") (pin "2") (pinfunction "2_2") (pintype "passive"))
      (node (ref "R15") (pin "2") (pinfunction "2_2") (pintype "passive"))
      (node (ref "R17") (pin "2") (pinfunction "2_2") (pintype "passive"))
      (node (ref "R18") (pin "2") (pinfunction "2_2") (pintype "passive"))
      (node (ref "R20") (pin "2") (pinfunction "2_2") (pintype "passive"))
      (node (ref "R21") (pin "2") (pinfunction "2_2") (pintype "passive"))
      (node (ref "R22") (pin "2") (pinfunction "2_2") (pintype "passive"))
      (node (ref "R25") (pin "2") (pinfunction "2_2") (pintype "passive"))
      (node (ref "R26") (pin "2") (pinfunction "2_2") (pintype "passive"))
      (node (ref "R27") (pin "2") (pinfunction "2_2") (pintype "passive"))
      (node (ref "R3") (pin "2") (pinfunction "2_2") (pintype "passive"))
      (node (ref "R30") (pin "2") (pinfunction "2_2") (pintype "passive"))
      (node (ref "R31") (pin "2") (pinfunction "2_2") (pintype "passive"))
      (node (ref "R32") (pin "2") (pinfunction "2_2") (pintype "passive"))
      (node (ref "R4") (pin "2") (pinfunction "2_2") (pintype "passive"))
      (node (ref "R5") (pin "2") (pinfunction "2_2") (pintype "passive"))
      (node (ref "U1") (pin "5") (pinfunction "AVDD_5") (pintype "power_in"))
      (node (ref "U1") (pin "8") (pinfunction "DVDD_8") (pintype "power_in"))
      (node (ref "U2") (pin "5") (pinfunction "AVDD_5") (pintype "power_in"))
      (node (ref "U2") (pin "8") (pinfunction "DVDD_8") (pintype "power_in"))
      (node (ref "U5") (pin "3") (pinfunction "VDD_3") (pintype "bidirectional"))
      (node (ref "U6") (pin "5") (pinfunction "AVDD_5") (pintype "power_in"))
      (node (ref "U6") (pin "8") (pinfunction "DVDD_8") (pintype "power_in"))
      (node (ref "U7") (pin "3") (pinfunction "VDD_3") (pintype "bidirectional"))
      (node (ref "U8") (pin "5") (pinfunction "AVDD_5") (pintype "power_in"))
      (node (ref "U8") (pin "8") (pinfunction "DVDD_8") (pintype "power_in"))
    )
    (net (code "51") (name "GND") (class "Default")
      (node (ref "B2") (pin "-") (pinfunction "-_-") (pintype "passive"))
      (node (ref "C1") (pin "1") (pinfunction "1_1") (pintype "passive"))
      (node (ref "C10") (pin "2") (pinfunction "2_2") (pintype "passive"))
      (node (ref "C11") (pin "2") (pinfunction "2_2") (pintype "passive"))
      (node (ref "C12") (pin "2") (pinfunction "2_2") (pintype "passive"))
      (node (ref "C13") (pin "2") (pinfunction "2_2") (pintype "passive"))
      (node (ref "C14") (pin "2") (pinfunction "2_2") (pintype "passive"))
      (node (ref "C15") (pin "2") (pinfunction "2_2") (pintype "passive"))
      (node (ref "C16") (pin "1") (pinfunction "1_1") (pintype "passive"))
      (node (ref "C18") (pin "2") (pinfunction "2_2") (pintype "passive"))
      (node (ref "C19") (pin "2") (pinfunction "2_2") (pintype "passive"))
      (node (ref "C20") (pin "2") (pinfunction "2_2") (pintype "passive"))
      (node (ref "C21") (pin "1") (pinfunction "1_1") (pintype "passive"))
      (node (ref "C23") (pin "2") (pinfunction "2_2") (pintype "passive"))
      (node (ref "C24") (pin "2") (pinfunction "2_2") (pintype "passive"))
      (node (ref "C25") (pin "2") (pinfunction "2_2") (pintype "passive"))
      (node (ref "C26") (pin "2") (pinfunction "2_2") (pintype "passive"))
      (node (ref "C3") (pin "2") (pinfunction "2_2") (pintype "passive"))
      (node (ref "C4") (pin "2") (pinfunction "2_2") (pintype "passive"))
      (node (ref "C5") (pin "2") (pinfunction "2_2") (pintype "passive"))
      (node (ref "C6") (pin "1") (pinfunction "1_1") (pintype "passive"))
      (node (ref "C8") (pin "2") (pinfunction "2_2") (pintype "passive"))
      (node (ref "C9") (pin "2") (pinfunction "2_2") (pintype "passive"))
      (node (ref "IC2") (pin "4") (pinfunction "VSS_4") (pintype "power_in"))
      (node (ref "JP1") (pin "7") (pinfunction "7_7") (pintype "passive"))
      (node (ref "JP10") (pin "7") (pinfunction "7_7") (pintype "passive"))
      (node (ref "JP11") (pin "2") (pinfunction "2_2") (pintype "passive"))
      (node (ref "JP2") (pin "7") (pinfunction "7_7") (pintype "passive"))
      (node (ref "JP6") (pin "7") (pinfunction "7_7") (pintype "passive"))
      (node (ref "JP7") (pin "2") (pinfunction "2_2") (pintype "passive"))
      (node (ref "JP7") (pin "3") (pinfunction "3_3") (pintype "passive"))
      (node (ref "JP8") (pin "7") (pinfunction "7_7") (pintype "passive"))
      (node (ref "LED1") (pin "C") (pinfunction "C_C") (pintype "passive"))
      (node (ref "LED2") (pin "C") (pinfunction "C_C") (pintype "passive"))
      (node (ref "LED3") (pin "C") (pinfunction "C_C") (pintype "passive"))
      (node (ref "LED4") (pin "C") (pinfunction "C_C") (pintype "passive"))
      (node (ref "R36") (pin "2") (pinfunction "2_2") (pintype "passive"))
      (node (ref "R37") (pin "2") (pinfunction "2_2") (pintype "passive"))
      (node (ref "R38") (pin "2") (pinfunction "2_2") (pintype "passive"))
      (node (ref "RESET") (pin "B") (pinfunction "S_B") (pintype "passive"))
      (node (ref "RESET") (pin "B'") (pinfunction "S1_B'") (pintype "passive"))
      (node (ref "U$14") (pin "3") (pinfunction "VSS1_3") (pintype "power_in"))
      (node (ref "U$14") (pin "6") (pinfunction "VSS2_6") (pintype "power_in"))
      (node (ref "U$14") (pin "GP") (pinfunction "GND_GP") (pintype "power_in"))
      (node (ref "U$14") (pin "GP3") (pinfunction "COMMON_SW_GP3") (pintype "passive"))
      (node (ref "U1") (pin "1") (pinfunction "AGND_1") (pintype "power_in"))
      (node (ref "U1") (pin "14") (pinfunction "DGND_14") (pintype "power_in"))
      (node (ref "U2") (pin "1") (pinfunction "AGND_1") (pintype "power_in"))
      (node (ref "U2") (pin "14") (pinfunction "DGND_14") (pintype "power_in"))
      (node (ref "U3") (pin "2") (pinfunction "GND_2") (pintype "power_in"))
      (node (ref "U4") (pin "8") (pinfunction "GND_8") (pintype "bidirectional"))
      (node (ref "U5") (pin "4") (pinfunction "VSS_4") (pintype "bidirectional"))
      (node (ref "U6") (pin "1") (pinfunction "AGND_1") (pintype "power_in"))
      (node (ref "U6") (pin "14") (pinfunction "DGND_14") (pintype "power_in"))
      (node (ref "U7") (pin "4") (pinfunction "VSS_4") (pintype "bidirectional"))
      (node (ref "U8") (pin "1") (pinfunction "AGND_1") (pintype "power_in"))
      (node (ref "U8") (pin "14") (pinfunction "DGND_14") (pintype "power_in"))
      (node (ref "U9") (pin "12") (pinfunction "GND_12") (pintype "bidirectional"))
    )
    (net (code "52") (name "Net-(IC2-VBAT)") (class "Default")
      (node (ref "B2") (pin "+$1") (pinfunction "+_+$1") (pintype "passive"))
      (node (ref "B2") (pin "+$2") (pinfunction "+_+$2") (pintype "passive"))
      (node (ref "IC2") (pin "3") (pinfunction "VBAT_3") (pintype "power_in"))
    )
    (net (code "53") (name "Net-(IC2-VDD)") (class "Default")
      (node (ref "C13") (pin "1") (pinfunction "1_1") (pintype "passive"))
      (node (ref "IC2") (pin "8") (pinfunction "VDD_8") (pintype "power_in"))
      (node (ref "R14") (pin "1") (pinfunction "1_1") (pintype "passive"))
    )
    (net (code "54") (name "Net-(IC2-XI)") (class "Default")
      (node (ref "IC2") (pin "1") (pinfunction "XI_1") (pintype "input"))
      (node (ref "Y2") (pin "P$4") (pinfunction "2_P$4") (pintype "passive"))
    )
    (net (code "55") (name "Net-(IC2-XO)") (class "Default")
      (node (ref "IC2") (pin "2") (pinfunction "XO_2") (pintype "output"))
      (node (ref "Y2") (pin "P$1") (pinfunction "1_P$1") (pintype "passive"))
    )
    (net (code "56") (name "Net-(JP3-Pad1)") (class "Default")
      (node (ref "JP3") (pin "1") (pinfunction "1_1") (pintype "passive"))
      (node (ref "R8") (pin "1") (pinfunction "1_1") (pintype "passive"))
    )
    (net (code "57") (name "Net-(JP3-Pad2)") (class "Default")
      (node (ref "JP3") (pin "2") (pinfunction "2_2") (pintype "passive"))
      (node (ref "R7") (pin "2") (pinfunction "2_2") (pintype "passive"))
    )
    (net (code "58") (name "Net-(JP9-Pad5)") (class "Default")
      (node (ref "JP9") (pin "5") (pinfunction "5_5") (pintype "passive"))
      (node (ref "SJ1") (pin "2") (pinfunction "2_2") (pintype "passive"))
      (node (ref "U$1") (pin "A4") (pinfunction "A4_A4") (pintype "bidirectional"))
    )
    (net (code "59") (name "Net-(JP9-Pad6)") (class "Default")
      (node (ref "JP9") (pin "6") (pinfunction "6_6") (pintype "passive"))
      (node (ref "SJ2") (pin "2") (pinfunction "2_2") (pintype "passive"))
      (node (ref "U$1") (pin "A5") (pinfunction "A5_A5") (pintype "bidirectional"))
    )
    (net (code "60") (name "Net-(LED1-PadA)") (class "Default")
      (node (ref "LED1") (pin "A") (pinfunction "A_A") (pintype "passive"))
      (node (ref "R8") (pin "2") (pinfunction "2_2") (pintype "passive"))
    )
    (net (code "61") (name "Net-(LED2-PadA)") (class "Default")
      (node (ref "LED2") (pin "A") (pinfunction "A_A") (pintype "passive"))
      (node (ref "R7") (pin "1") (pinfunction "1_1") (pintype "passive"))
    )
    (net (code "62") (name "Net-(LED3-PadA)") (class "Default")
      (node (ref "LED3") (pin "A") (pinfunction "A_A") (pintype "passive"))
      (node (ref "R11") (pin "1") (pinfunction "1_1") (pintype "passive"))
    )
    (net (code "63") (name "Net-(LED4-PadA)") (class "Default")
      (node (ref "LED4") (pin "A") (pinfunction "A_A") (pintype "passive"))
      (node (ref "R12") (pin "1") (pinfunction "1_1") (pintype "passive"))
    )
    (net (code "64") (name "Net-(R2-Pad1)") (class "Default")
      (node (ref "R2") (pin "1") (pinfunction "1_1") (pintype "passive"))
      (node (ref "X1") (pin "1") (pinfunction "1_1") (pintype "passive"))
    )
    (net (code "65") (name "Net-(R19-Pad1)") (class "Default")
      (node (ref "R19") (pin "1") (pinfunction "1_1") (pintype "passive"))
      (node (ref "X2") (pin "1") (pinfunction "1_1") (pintype "passive"))
    )
    (net (code "66") (name "Net-(R24-Pad1)") (class "Default")
      (node (ref "R24") (pin "1") (pinfunction "1_1") (pintype "passive"))
      (node (ref "X3") (pin "1") (pinfunction "1_1") (pintype "passive"))
    )
    (net (code "67") (name "Net-(R29-Pad1)") (class "Default")
      (node (ref "R29") (pin "1") (pinfunction "1_1") (pintype "passive"))
      (node (ref "X4") (pin "1") (pinfunction "1_1") (pintype "passive"))
    )
    (net (code "68") (name "Net-(R33-Pad1)") (class "Default")
      (node (ref "R33") (pin "1") (pinfunction "1_1") (pintype "passive"))
      (node (ref "SDAPU") (pin "2") (pinfunction "2_2") (pintype "passive"))
    )
    (net (code "69") (name "Net-(R34-Pad1)") (class "Default")
      (node (ref "R34") (pin "1") (pinfunction "1_1") (pintype "passive"))
      (node (ref "SCLPU") (pin "2") (pinfunction "2_2") (pintype "passive"))
    )
    (net (code "70") (name "Net-(U$14-CARD_DETECT)") (class "Default")
      (node (ref "CN1") (pin "1") (pinfunction "1_1") (pintype "bidirectional"))
      (node (ref "U$14") (pin "CD") (pinfunction "CARD_DETECT_CD") (pintype "passive"))
    )
    (net (code "71") (name "Net-(U$14-WRITE_PROTECT)") (class "Default")
      (node (ref "CN1") (pin "2") (pinfunction "2_2") (pintype "bidirectional"))
      (node (ref "U$14") (pin "WP") (pinfunction "WRITE_PROTECT_WP") (pintype "passive"))
    )
    (net (code "72") (name "Net-(U1-SCK)") (class "Default")
      (node (ref "D5") (pin "A") (pinfunction "A_A") (pintype "passive"))
      (node (ref "R21") (pin "1") (pinfunction "1_1") (pintype "passive"))
      (node (ref "U1") (pin "10") (pinfunction "SCK_10") (pintype "input"))
    )
    (net (code "73") (name "Net-(U1-SDI)") (class "Default")
      (node (ref "D6") (pin "A") (pinfunction "A_A") (pintype "passive"))
      (node (ref "R20") (pin "1") (pinfunction "1_1") (pintype "passive"))
      (node (ref "U1") (pin "12") (pinfunction "SDI_12") (pintype "input"))
    )
    (net (code "74") (name "Net-(U1-~{CS})") (class "Default")
      (node (ref "D4") (pin "A") (pinfunction "A_A") (pintype "passive"))
      (node (ref "R22") (pin "1") (pinfunction "1_1") (pintype "passive"))
      (node (ref "U1") (pin "9") (pinfunction "~{CS}_9") (pintype "input"))
    )
    (net (code "75") (name "Net-(U2-SCK)") (class "Default")
      (node (ref "D2") (pin "A") (pinfunction "A_A") (pintype "passive"))
      (node (ref "R4") (pin "1") (pinfunction "1_1") (pintype "passive"))
      (node (ref "U2") (pin "10") (pinfunction "SCK_10") (pintype "input"))
    )
    (net (code "76") (name "Net-(U2-SDI)") (class "Default")
      (node (ref "D3") (pin "A") (pinfunction "A_A") (pintype "passive"))
      (node (ref "R3") (pin "1") (pinfunction "1_1") (pintype "passive"))
      (node (ref "U2") (pin "12") (pinfunction "SDI_12") (pintype "input"))
    )
    (net (code "77") (name "Net-(U2-~{CS})") (class "Default")
      (node (ref "D1") (pin "A") (pinfunction "A_A") (pintype "passive"))
      (node (ref "R5") (pin "1") (pinfunction "1_1") (pintype "passive"))
      (node (ref "U2") (pin "9") (pinfunction "~{CS}_9") (pintype "input"))
    )
    (net (code "78") (name "Net-(U6-SCK)") (class "Default")
      (node (ref "D8") (pin "A") (pinfunction "A_A") (pintype "passive"))
      (node (ref "R26") (pin "1") (pinfunction "1_1") (pintype "passive"))
      (node (ref "U6") (pin "10") (pinfunction "SCK_10") (pintype "input"))
    )
    (net (code "79") (name "Net-(U6-SDI)") (class "Default")
      (node (ref "D9") (pin "A") (pinfunction "A_A") (pintype "passive"))
      (node (ref "R25") (pin "1") (pinfunction "1_1") (pintype "passive"))
      (node (ref "U6") (pin "12") (pinfunction "SDI_12") (pintype "input"))
    )
    (net (code "80") (name "Net-(U6-~{CS})") (class "Default")
      (node (ref "D7") (pin "A") (pinfunction "A_A") (pintype "passive"))
      (node (ref "R27") (pin "1") (pinfunction "1_1") (pintype "passive"))
      (node (ref "U6") (pin "9") (pinfunction "~{CS}_9") (pintype "input"))
    )
    (net (code "81") (name "Net-(U8-SCK)") (class "Default")
      (node (ref "D11") (pin "A") (pinfunction "A_A") (pintype "passive"))
      (node (ref "R31") (pin "1") (pinfunction "1_1") (pintype "passive"))
      (node (ref "U8") (pin "10") (pinfunction "SCK_10") (pintype "input"))
    )
    (net (code "82") (name "Net-(U8-SDI)") (class "Default")
      (node (ref "D12") (pin "A") (pinfunction "A_A") (pintype "passive"))
      (node (ref "R30") (pin "1") (pinfunction "1_1") (pintype "passive"))
      (node (ref "U8") (pin "12") (pinfunction "SDI_12") (pintype "input"))
    )
    (net (code "83") (name "Net-(U8-~{CS})") (class "Default")
      (node (ref "D10") (pin "A") (pinfunction "A_A") (pintype "passive"))
      (node (ref "R32") (pin "1") (pinfunction "1_1") (pintype "passive"))
      (node (ref "U8") (pin "9") (pinfunction "~{CS}_9") (pintype "input"))
    )
    (net (code "84") (name "VCC") (class "Default")
      (node (ref "A0") (pin "2") (pinfunction "2_2") (pintype "passive"))
      (node (ref "A1") (pin "2") (pinfunction "2_2") (pintype "passive"))
      (node (ref "A2") (pin "1") (pinfunction "1_1") (pintype "passive"))
      (node (ref "C26") (pin "1") (pinfunction "1_1") (pintype "passive"))
      (node (ref "JP11") (pin "1") (pinfunction "1_1") (pintype "passive"))
      (node (ref "R33") (pin "2") (pinfunction "2_2") (pintype "passive"))
      (node (ref "R34") (pin "2") (pinfunction "2_2") (pintype "passive"))
      (node (ref "R35") (pin "2") (pinfunction "2_2") (pintype "passive"))
      (node (ref "U9") (pin "24") (pinfunction "VCC_24") (pintype "bidirectional"))
    )
    (net (code "85") (name "VDDIO") (class "Default")
      (node (ref "R10") (pin "1") (pinfunction "1_1") (pintype "passive"))
      (node (ref "R14") (pin "2") (pinfunction "2_2") (pintype "passive"))
      (node (ref "R6") (pin "1") (pinfunction "1_1") (pintype "passive"))
      (node (ref "R9") (pin "1") (pinfunction "1_1") (pintype "passive"))
      (node (ref "SJ7") (pin "2") (pinfunction "2_2") (pintype "passive"))
    )
    (net (code "86") (name "VIN") (class "Default")
      (node (ref "JP1") (pin "9") (pinfunction "9_9") (pintype "passive"))
      (node (ref "JP10") (pin "9") (pinfunction "9_9") (pintype "passive"))
      (node (ref "JP6") (pin "9") (pinfunction "9_9") (pintype "passive"))
      (node (ref "JP8") (pin "9") (pinfunction "9_9") (pintype "passive"))
    )
    (net (code "87") (name "unconnected-(JP2-Pad1)") (class "Default")
      (node (ref "JP2") (pin "1") (pinfunction "1_1") (pintype "passive"))
    )
    (net (code "88") (name "unconnected-(JP2-Pad2)") (class "Default")
      (node (ref "JP2") (pin "2") (pinfunction "2_2") (pintype "passive"))
    )
    (net (code "89") (name "unconnected-(JP2-Pad8)") (class "Default")
      (node (ref "JP2") (pin "8") (pinfunction "8_8") (pintype "passive"))
    )
    (net (code "90") (name "unconnected-(JP4-Pad1)") (class "Default")
      (node (ref "JP4") (pin "1") (pinfunction "1_1") (pintype "passive"))
    )
    (net (code "91") (name "unconnected-(JP4-Pad2)") (class "Default")
      (node (ref "JP4") (pin "2") (pinfunction "2_2") (pintype "passive"))
    )
    (net (code "92") (name "unconnected-(JP4-Pad3)") (class "Default")
      (node (ref "JP4") (pin "3") (pinfunction "3_3") (pintype "passive"))
    )
    (net (code "93") (name "unconnected-(JP4-Pad4)") (class "Default")
      (node (ref "JP4") (pin "4") (pinfunction "4_4") (pintype "passive"))
    )
    (net (code "94") (name "unconnected-(JP4-Pad5)") (class "Default")
      (node (ref "JP4") (pin "5") (pinfunction "5_5") (pintype "passive"))
    )
    (net (code "95") (name "unconnected-(JP4-Pad6)") (class "Default")
      (node (ref "JP4") (pin "6") (pinfunction "6_6") (pintype "passive"))
    )
    (net (code "96") (name "unconnected-(JP4-Pad7)") (class "Default")
      (node (ref "JP4") (pin "7") (pinfunction "7_7") (pintype "passive"))
    )
    (net (code "97") (name "unconnected-(JP4-Pad8)") (class "Default")
      (node (ref "JP4") (pin "8") (pinfunction "8_8") (pintype "passive"))
    )
    (net (code "98") (name "unconnected-(JP7-Pad1)") (class "Default")
      (node (ref "JP7") (pin "1") (pinfunction "1_1") (pintype "passive"))
    )
    (net (code "99") (name "unconnected-(JP7-Pad5)") (class "Default")
      (node (ref "JP7") (pin "5") (pinfunction "5_5") (pintype "passive"))
    )
    (net (code "100") (name "unconnected-(JP9-Pad1)") (class "Default")
      (node (ref "JP9") (pin "1") (pinfunction "1_1") (pintype "passive"))
    )
    (net (code "101") (name "unconnected-(JP9-Pad2)") (class "Default")
      (node (ref "JP9") (pin "2") (pinfunction "2_2") (pintype "passive"))
    )
    (net (code "102") (name "unconnected-(JP9-Pad3)") (class "Default")
      (node (ref "JP9") (pin "3") (pinfunction "3_3") (pintype "passive"))
    )
    (net (code "103") (name "unconnected-(JP9-Pad4)") (class "Default")
      (node (ref "JP9") (pin "4") (pinfunction "4_4") (pintype "passive"))
    )
    (net (code "104") (name "unconnected-(U$1-GND-PadGND@1)") (class "Default")
      (node (ref "U$1") (pin "GND@1") (pinfunction "GND_GND@1") (pintype "bidirectional"))
    )
    (net (code "105") (name "unconnected-(U$1-GND-PadGND@2)") (class "Default")
      (node (ref "U$1") (pin "GND@2") (pinfunction "GND_GND@2") (pintype "bidirectional"))
    )
    (net (code "106") (name "unconnected-(U$1-GND-PadGND@3)") (class "Default")
      (node (ref "U$1") (pin "GND@3") (pinfunction "GND_GND@3") (pintype "bidirectional"))
    )
    (net (code "107") (name "unconnected-(U$1-GND-PadGND@4)") (class "Default")
      (node (ref "U$1") (pin "GND@4") (pinfunction "GND_GND@4") (pintype "bidirectional"))
    )
    (net (code "108") (name "unconnected-(U$1-GND-PadGND@5)") (class "Default")
      (node (ref "U$1") (pin "GND@5") (pinfunction "GND_GND@5") (pintype "bidirectional"))
    )
    (net (code "109") (name "unconnected-(U$1-GND-PadGND@6)") (class "Default")
      (node (ref "U$1") (pin "GND@6") (pinfunction "GND_GND@6") (pintype "bidirectional"))
    )
    (net (code "110") (name "unconnected-(U$1-GND-PadGND@7)") (class "Default")
      (node (ref "U$1") (pin "GND@7") (pinfunction "GND_GND@7") (pintype "bidirectional"))
    )
    (net (code "111") (name "unconnected-(U$1-Pad0)") (class "Default")
      (node (ref "U$1") (pin "0") (pinfunction "0_0") (pintype "bidirectional"))
    )
    (net (code "112") (name "unconnected-(U$1-Pad1)") (class "Default")
      (node (ref "U$1") (pin "1") (pinfunction "1_1") (pintype "bidirectional"))
    )
    (net (code "113") (name "unconnected-(U$1-Pad2)") (class "Default")
      (node (ref "U$1") (pin "2") (pinfunction "2_2") (pintype "bidirectional"))
    )
    (net (code "114") (name "unconnected-(U$1-Pad3)") (class "Default")
      (node (ref "U$1") (pin "3") (pinfunction "3_3") (pintype "bidirectional"))
    )
    (net (code "115") (name "unconnected-(U$1-Pad3V3)") (class "Default")
      (node (ref "U$1") (pin "3V3") (pinfunction "3V3_3V3") (pintype "bidirectional"))
    )
    (net (code "116") (name "unconnected-(U$1-Pad4)") (class "Default")
      (node (ref "U$1") (pin "4") (pinfunction "4_4") (pintype "bidirectional"))
    )
    (net (code "117") (name "unconnected-(U$1-Pad5)") (class "Default")
      (node (ref "U$1") (pin "5") (pinfunction "5_5") (pintype "bidirectional"))
    )
    (net (code "118") (name "unconnected-(U$1-Pad5V)") (class "Default")
      (node (ref "U$1") (pin "5V") (pinfunction "5V_5V") (pintype "bidirectional"))
    )
    (net (code "119") (name "unconnected-(U$1-Pad6)") (class "Default")
      (node (ref "U$1") (pin "6") (pinfunction "6_6") (pintype "bidirectional"))
    )
    (net (code "120") (name "unconnected-(U$1-Pad7)") (class "Default")
      (node (ref "U$1") (pin "7") (pinfunction "7_7") (pintype "bidirectional"))
    )
    (net (code "121") (name "unconnected-(U$1-Pad8)") (class "Default")
      (node (ref "U$1") (pin "8") (pinfunction "8_8") (pintype "bidirectional"))
    )
    (net (code "122") (name "unconnected-(U$1-Pad9)") (class "Default")
      (node (ref "U$1") (pin "9") (pinfunction "9_9") (pintype "bidirectional"))
    )
    (net (code "123") (name "unconnected-(U$1-Pad10)") (class "Default")
      (node (ref "U$1") (pin "10") (pinfunction "10_10") (pintype "bidirectional"))
    )
    (net (code "124") (name "unconnected-(U$1-Pad11)") (class "Default")
      (node (ref "U$1") (pin "11") (pinfunction "11_11") (pintype "bidirectional"))
    )
    (net (code "125") (name "unconnected-(U$1-Pad12)") (class "Default")
      (node (ref "U$1") (pin "12") (pinfunction "12_12") (pintype "bidirectional"))
    )
    (net (code "126") (name "unconnected-(U$1-Pad13)") (class "Default")
      (node (ref "U$1") (pin "13") (pinfunction "13_13") (pintype "bidirectional"))
    )
    (net (code "127") (name "unconnected-(U$1-Pad14)") (class "Default")
      (node (ref "U$1") (pin "14") (pinfunction "14_14") (pintype "bidirectional"))
    )
    (net (code "128") (name "unconnected-(U$1-Pad15)") (class "Default")
      (node (ref "U$1") (pin "15") (pinfunction "15_15") (pintype "bidirectional"))
    )
    (net (code "129") (name "unconnected-(U$1-Pad16)") (class "Default")
      (node (ref "U$1") (pin "16") (pinfunction "16_16") (pintype "bidirectional"))
    )
    (net (code "130") (name "unconnected-(U$1-Pad17)") (class "Default")
      (node (ref "U$1") (pin "17") (pinfunction "17_17") (pintype "bidirectional"))
    )
    (net (code "131") (name "unconnected-(U$1-Pad18)") (class "Default")
      (node (ref "U$1") (pin "18") (pinfunction "18_18") (pintype "bidirectional"))
    )
    (net (code "132") (name "unconnected-(U$1-Pad19)") (class "Default")
      (node (ref "U$1") (pin "19") (pinfunction "19_19") (pintype "bidirectional"))
    )
    (net (code "133") (name "unconnected-(U$1-Pad20)") (class "Default")
      (node (ref "U$1") (pin "20") (pinfunction "20_20") (pintype "bidirectional"))
    )
    (net (code "134") (name "unconnected-(U$1-Pad21)") (class "Default")
      (node (ref "U$1") (pin "21") (pinfunction "21_21") (pintype "bidirectional"))
    )
    (net (code "135") (name "unconnected-(U$1-Pad22)") (class "Default")
      (node (ref "U$1") (pin "22") (pinfunction "22_22") (pintype "bidirectional"))
    )
    (net (code "136") (name "unconnected-(U$1-Pad23)") (class "Default")
      (node (ref "U$1") (pin "23") (pinfunction "23_23") (pintype "bidirectional"))
    )
    (net (code "137") (name "unconnected-(U$1-Pad24)") (class "Default")
      (node (ref "U$1") (pin "24") (pinfunction "24_24") (pintype "bidirectional"))
    )
    (net (code "138") (name "unconnected-(U$1-Pad25)") (class "Default")
      (node (ref "U$1") (pin "25") (pinfunction "25_25") (pintype "bidirectional"))
    )
    (net (code "139") (name "unconnected-(U$1-Pad26)") (class "Default")
      (node (ref "U$1") (pin "26") (pinfunction "26_26") (pintype "bidirectional"))
    )
    (net (code "140") (name "unconnected-(U$1-Pad27)") (class "Default")
      (node (ref "U$1") (pin "27") (pinfunction "27_27") (pintype "bidirectional"))
    )
    (net (code "141") (name "unconnected-(U$1-Pad28)") (class "Default")
      (node (ref "U$1") (pin "28") (pinfunction "28_28") (pintype "bidirectional"))
    )
    (net (code "142") (name "unconnected-(U$1-Pad29)") (class "Default")
      (node (ref "U$1") (pin "29") (pinfunction "29_29") (pintype "bidirectional"))
    )
    (net (code "143") (name "unconnected-(U$1-Pad30)") (class "Default")
      (node (ref "U$1") (pin "30") (pinfunction "30_30") (pintype "bidirectional"))
    )
    (net (code "144") (name "unconnected-(U$1-Pad31)") (class "Default")
      (node (ref "U$1") (pin "31") (pinfunction "31_31") (pintype "bidirectional"))
    )
    (net (code "145") (name "unconnected-(U$1-Pad32)") (class "Default")
      (node (ref "U$1") (pin "32") (pinfunction "32_32") (pintype "bidirectional"))
    )
    (net (code "146") (name "unconnected-(U$1-Pad33)") (class "Default")
      (node (ref "U$1") (pin "33") (pinfunction "33_33") (pintype "bidirectional"))
    )
    (net (code "147") (name "unconnected-(U$1-Pad34)") (class "Default")
      (node (ref "U$1") (pin "34") (pinfunction "34_34") (pintype "bidirectional"))
    )
    (net (code "148") (name "unconnected-(U$1-Pad35)") (class "Default")
      (node (ref "U$1") (pin "35") (pinfunction "35_35") (pintype "bidirectional"))
    )
    (net (code "149") (name "unconnected-(U$1-Pad36)") (class "Default")
      (node (ref "U$1") (pin "36") (pinfunction "36_36") (pintype "bidirectional"))
    )
    (net (code "150") (name "unconnected-(U$1-Pad37)") (class "Default")
      (node (ref "U$1") (pin "37") (pinfunction "37_37") (pintype "bidirectional"))
    )
    (net (code "151") (name "unconnected-(U$1-Pad38)") (class "Default")
      (node (ref "U$1") (pin "38") (pinfunction "38_38") (pintype "bidirectional"))
    )
    (net (code "152") (name "unconnected-(U$1-Pad39)") (class "Default")
      (node (ref "U$1") (pin "39") (pinfunction "39_39") (pintype "bidirectional"))
    )
    (net (code "153") (name "unconnected-(U$1-Pad40)") (class "Default")
      (node (ref "U$1") (pin "40") (pinfunction "40_40") (pintype "bidirectional"))
    )
    (net (code "154") (name "unconnected-(U$1-Pad41)") (class "Default")
      (node (ref "U$1") (pin "41") (pinfunction "41_41") (pintype "bidirectional"))
    )
    (net (code "155") (name "unconnected-(U$1-Pad42)") (class "Default")
      (node (ref "U$1") (pin "42") (pinfunction "42_42") (pintype "bidirectional"))
    )
    (net (code "156") (name "unconnected-(U$1-Pad43)") (class "Default")
      (node (ref "U$1") (pin "43") (pinfunction "43_43") (pintype "bidirectional"))
    )
    (net (code "157") (name "unconnected-(U$1-Pad44)") (class "Default")
      (node (ref "U$1") (pin "44") (pinfunction "44_44") (pintype "bidirectional"))
    )
    (net (code "158") (name "unconnected-(U$1-Pad45)") (class "Default")
      (node (ref "U$1") (pin "45") (pinfunction "45_45") (pintype "bidirectional"))
    )
    (net (code "159") (name "unconnected-(U$1-Pad46)") (class "Default")
      (node (ref "U$1") (pin "46") (pinfunction "46_46") (pintype "bidirectional"))
    )
    (net (code "160") (name "unconnected-(U$1-Pad47)") (class "Default")
      (node (ref "U$1") (pin "47") (pinfunction "47_47") (pintype "bidirectional"))
    )
    (net (code "161") (name "unconnected-(U$1-Pad48)") (class "Default")
      (node (ref "U$1") (pin "48") (pinfunction "48_48") (pintype "bidirectional"))
    )
    (net (code "162") (name "unconnected-(U$1-Pad49)") (class "Default")
      (node (ref "U$1") (pin "49") (pinfunction "49_49") (pintype "bidirectional"))
    )
    (net (code "163") (name "unconnected-(U$1-PadA0)") (class "Default")
      (node (ref "U$1") (pin "A0") (pinfunction "A0_A0") (pintype "bidirectional"))
    )
    (net (code "164") (name "unconnected-(U$1-PadA1)") (class "Default")
      (node (ref "U$1") (pin "A1") (pinfunction "A1_A1") (pintype "bidirectional"))
    )
    (net (code "165") (name "unconnected-(U$1-PadA2)") (class "Default")
      (node (ref "U$1") (pin "A2") (pinfunction "A2_A2") (pintype "bidirectional"))
    )
    (net (code "166") (name "unconnected-(U$1-PadA3)") (class "Default")
      (node (ref "U$1") (pin "A3") (pinfunction "A3_A3") (pintype "bidirectional"))
    )
    (net (code "167") (name "unconnected-(U$1-PadA6)") (class "Default")
      (node (ref "U$1") (pin "A6") (pinfunction "A6_A6") (pintype "bidirectional"))
    )
    (net (code "168") (name "unconnected-(U$1-PadA7)") (class "Default")
      (node (ref "U$1") (pin "A7") (pinfunction "A7_A7") (pintype "bidirectional"))
    )
    (net (code "169") (name "unconnected-(U$1-PadA8)") (class "Default")
      (node (ref "U$1") (pin "A8") (pinfunction "A8_A8") (pintype "bidirectional"))
    )
    (net (code "170") (name "unconnected-(U$1-PadA9)") (class "Default")
      (node (ref "U$1") (pin "A9") (pinfunction "A9_A9") (pintype "bidirectional"))
    )
    (net (code "171") (name "unconnected-(U$1-PadA10)") (class "Default")
      (node (ref "U$1") (pin "A10") (pinfunction "A10_A10") (pintype "bidirectional"))
    )
    (net (code "172") (name "unconnected-(U$1-PadA11)") (class "Default")
      (node (ref "U$1") (pin "A11") (pinfunction "A11_A11") (pintype "bidirectional"))
    )
    (net (code "173") (name "unconnected-(U$1-PadA12)") (class "Default")
      (node (ref "U$1") (pin "A12") (pinfunction "A12_A12") (pintype "bidirectional"))
    )
    (net (code "174") (name "unconnected-(U$1-PadA13)") (class "Default")
      (node (ref "U$1") (pin "A13") (pinfunction "A13_A13") (pintype "bidirectional"))
    )
    (net (code "175") (name "unconnected-(U$1-PadA14)") (class "Default")
      (node (ref "U$1") (pin "A14") (pinfunction "A14_A14") (pintype "bidirectional"))
    )
    (net (code "176") (name "unconnected-(U$1-PadA15)") (class "Default")
      (node (ref "U$1") (pin "A15") (pinfunction "A15_A15") (pintype "bidirectional"))
    )
    (net (code "177") (name "unconnected-(U$1-PadAREF)") (class "Default")
      (node (ref "U$1") (pin "AREF") (pinfunction "AREF_AREF") (pintype "bidirectional"))
    )
    (net (code "178") (name "unconnected-(U$1-PadRESET)") (class "Default")
      (node (ref "U$1") (pin "RESET") (pinfunction "RESET_RESET") (pintype "bidirectional"))
    )
    (net (code "179") (name "unconnected-(U$1-PadVIN)") (class "Default")
      (node (ref "U$1") (pin "VIN") (pinfunction "VIN_VIN") (pintype "bidirectional"))
    )
    (net (code "180") (name "unconnected-(U$14-DAT1-Pad8)") (class "Default")
      (node (ref "U$14") (pin "8") (pinfunction "DAT1_8") (pintype "bidirectional"))
    )
    (net (code "181") (name "unconnected-(U$14-DAT2-Pad9)") (class "Default")
      (node (ref "U$14") (pin "9") (pinfunction "DAT2_9") (pintype "bidirectional"))
    )
    (net (code "182") (name "unconnected-(U1-DNC-Pad6)") (class "Default")
      (node (ref "U1") (pin "6") (pinfunction "DNC_6") (pintype "no_connect"))
    )
    (net (code "183") (name "unconnected-(U2-DNC-Pad6)") (class "Default")
      (node (ref "U2") (pin "6") (pinfunction "DNC_6") (pintype "no_connect"))
    )
    (net (code "184") (name "unconnected-(U3-P4-Pad4)") (class "Default")
      (node (ref "U3") (pin "4") (pinfunction "P4_4") (pintype "bidirectional"))
    )
    (net (code "185") (name "unconnected-(U4-2A-Pad5)") (class "Default")
      (node (ref "U4") (pin "5") (pinfunction "2A_5") (pintype "bidirectional"))
    )
    (net (code "186") (name "unconnected-(U4-2Y-Pad4)") (class "Default")
      (node (ref "U4") (pin "4") (pinfunction "2Y_4") (pintype "bidirectional"))
    )
    (net (code "187") (name "unconnected-(U4-5A-Pad11)") (class "Default")
      (node (ref "U4") (pin "11") (pinfunction "5A_11") (pintype "bidirectional"))
    )
    (net (code "188") (name "unconnected-(U4-5Y-Pad12)") (class "Default")
      (node (ref "U4") (pin "12") (pinfunction "5Y_12") (pintype "bidirectional"))
    )
    (net (code "189") (name "unconnected-(U4-6A-Pad14)") (class "Default")
      (node (ref "U4") (pin "14") (pinfunction "6A_14") (pintype "bidirectional"))
    )
    (net (code "190") (name "unconnected-(U4-6Y-Pad15)") (class "Default")
      (node (ref "U4") (pin "15") (pinfunction "6Y_15") (pintype "bidirectional"))
    )
    (net (code "191") (name "unconnected-(U6-DNC-Pad6)") (class "Default")
      (node (ref "U6") (pin "6") (pinfunction "DNC_6") (pintype "no_connect"))
    )
    (net (code "192") (name "unconnected-(U8-DNC-Pad6)") (class "Default")
      (node (ref "U8") (pin "6") (pinfunction "DNC_6") (pintype "no_connect"))
    )
  )
)
